# lna.net
KiCad netlist of a schematic drawn in Altium Designer
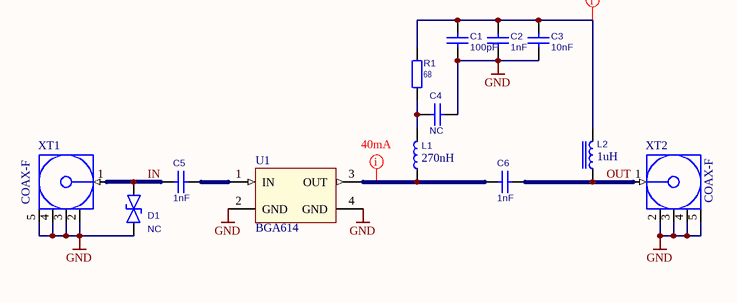
[diagram p0: lna.SchDoc]

(export (version "E")
  (design (tool "Eeschema 10.0.6"))
  (components
    (comp (ref "C1")
      (value "100pF")
      (footprint "Capacitors:C0805")
      (description "CAP_NPOL")
      (libsource (lib "capacitors") (part "CAP_NPOL"))
    )
    (comp (ref "C2")
      (value "1nF")
      (footprint "Capacitors:C0805")
      (description "CAP_NPOL")
      (libsource (lib "capacitors") (part "CAP_NPOL"))
    )
    (comp (ref "C3")
      (value "10nF")
      (footprint "Capacitors:C0805")
      (description "CAP_NPOL")
      (libsource (lib "capacitors") (part "CAP_NPOL"))
    )
    (comp (ref "C4")
      (value "NC")
      (footprint "Capacitors:C0805")
      (description "CAP_NPOL")
      (libsource (lib "capacitors") (part "CAP_NPOL"))
    )
    (comp (ref "C5")
      (value "1nF")
      (footprint "C1210")
      (description "CAP_NPOL")
      (libsource (lib "capacitors") (part "CAP_NPOL"))
    )
    (comp (ref "C6")
      (value "1nF")
      (footprint "C1210")
      (description "CAP_NPOL")
      (libsource (lib "capacitors") (part "CAP_NPOL"))
    )
    (comp (ref "D1")
      (value "NC")
      (footprint "SOD-323")
      (description "TVS Diodes")
      (libsource (lib "diodes") (part "TVS_BIDIR"))
    )
    (comp (ref "L1")
      (value "270nH")
      (footprint "IND0603")
      (description "IND_WO_IRON")
      (libsource (lib "inductors") (part "IND_WO_IRON"))
    )
    (comp (ref "L2")
      (value "1uH")
      (footprint "IND0805")
      (description "IND_W_IRON")
      (libsource (lib "inductors") (part "IND_W_IRON"))
    )
    (comp (ref "R1")
      (value "68")
      (footprint "Resistors:R0805")
      (description "RES")
      (libsource (lib "resistors") (part "RESISTOR"))
    )
    (comp (ref "U1")
      (value "BGA614")
      (footprint "SOT-343")
      (description "Silicon Germanium Broadband MMIC Amplifier")
      (libsource (lib "BGA614") (part "BGA614"))
    )
    (comp (ref "XT1")
      (value "COAX-F")
      (footprint "RF:SMA-16")
      (fields (field (name "PUBLISHER") "Altium Limited"))
      (libsource (lib "Miscellaneous Connectors") (part "COAX-F"))
    )
    (comp (ref "XT2")
      (value "COAX-F")
      (footprint "RF:SMA-16")
      (fields (field (name "PUBLISHER") "Altium Limited"))
      (libsource (lib "Miscellaneous Connectors") (part "COAX-F"))
    )
  )
  (nets
    (net (code "1") (name "/IN") (class "Default")
      (node (ref "C5") (pin "1") (pinfunction "1_1") (pintype "passive"))
      (node (ref "D1") (pin "2") (pinfunction "2_2") (pintype "passive"))
      (node (ref "XT1") (pin "1") (pinfunction "Signal_1") (pintype "input"))
    )
    (net (code "2") (name "/OUT") (class "Default")
      (node (ref "C6") (pin "2") (pinfunction "2_2") (pintype "passive"))
      (node (ref "L2") (pin "1") (pintype "passive"))
      (node (ref "XT2") (pin "1") (pinfunction "Signal_1") (pintype "input"))
    )
    (net (code "3") (name "GND") (class "Default")
      (node (ref "C1") (pin "1") (pinfunction "1_1") (pintype "passive"))
      (node (ref "C2") (pin "1") (pinfunction "1_1") (pintype "passive"))
      (node (ref "C3") (pin "1") (pinfunction "1_1") (pintype "passive"))
      (node (ref "C4") (pin "2") (pinfunction "2_2") (pintype "passive"))
      (node (ref "D1") (pin "1") (pinfunction "1_1") (pintype "passive"))
      (node (ref "U1") (pin "2") (pinfunction "GND_2") (pintype "power_in"))
      (node (ref "U1") (pin "4") (pinfunction "GND_4") (pintype "power_in"))
      (node (ref "XT1") (pin "2") (pinfunction "GND_2") (pintype "power_in"))
      (node (ref "XT1") (pin "3") (pinfunction "GND_3") (pintype "power_in"))
      (node (ref "XT1") (pin "4") (pinfunction "GND_4") (pintype "power_in"))
      (node (ref "XT1") (pin "5") (pinfunction "GND_5") (pintype "power_in"))
      (node (ref "XT2") (pin "2") (pinfunction "GND_2") (pintype "power_in"))
      (node (ref "XT2") (pin "3") (pinfunction "GND_3") (pintype "power_in"))
      (node (ref "XT2") (pin "4") (pinfunction "GND_4") (pintype "power_in"))
      (node (ref "XT2") (pin "5") (pinfunction "GND_5") (pintype "power_in"))
    )
    (net (code "4") (name "Net-(C1-Pad2)") (class "Default")
      (node (ref "C1") (pin "2") (pinfunction "2_2") (pintype "passive"))
      (node (ref "C2") (pin "2") (pinfunction "2_2") (pintype "passive"))
      (node (ref "C3") (pin "2") (pinfunction "2_2") (pintype "passive"))
      (node (ref "L2") (pin "2") (pintype "passive"))
      (node (ref "R1") (pin "2") (pinfunction "2_2") (pintype "passive"))
    )
    (net (code "5") (name "Net-(C4-Pad1)") (class "Default")
      (node (ref "C4") (pin "1") (pinfunction "1_1") (pintype "passive"))
      (node (ref "L1") (pin "2") (pintype "passive"))
      (node (ref "R1") (pin "1") (pinfunction "1_1") (pintype "passive"))
    )
    (net (code "6") (name "Net-(U1-IN)") (class "Default")
      (node (ref "C5") (pin "2") (pinfunction "2_2") (pintype "passive"))
      (node (ref "U1") (pin "1") (pinfunction "IN_1") (pintype "input"))
    )
    (net (code "7") (name "Net-(U1-OUT)") (class "Default")
      (node (ref "C6") (pin "1") (pinfunction "1_1") (pintype "passive"))
      (node (ref "L1") (pin "1") (pintype "passive"))
      (node (ref "U1") (pin "3") (pinfunction "OUT_3") (pintype "output"))
    )
  )
)
